# relay_driver.net
KiCad netlist of a schematic drawn in EAGLE
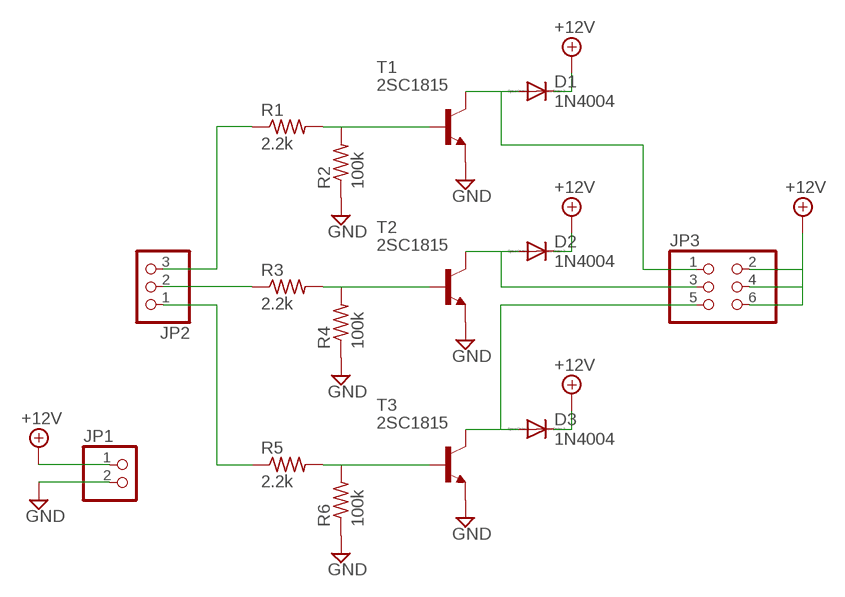
[diagram p0: schematic, sheet 1]

(export (version "E")
  (design (tool "Eeschema 10.0.6"))
  (components
    (comp (ref "D1")
      (value "1N4004")
      (footprint "eagle-import:DO41-10")
      (libsource (lib "eagle-import") (part "1N4004"))
    )
    (comp (ref "D2")
      (value "1N4004")
      (footprint "eagle-import:DO41-10")
      (libsource (lib "eagle-import") (part "1N4004"))
    )
    (comp (ref "D3")
      (value "1N4004")
      (footprint "eagle-import:DO41-10")
      (libsource (lib "eagle-import") (part "1N4004"))
    )
    (comp (ref "JP1")
      (value "PINHD-1X2")
      (footprint "eagle-import:1X02")
      (libsource (lib "eagle-import") (part "PINHD-1X2"))
    )
    (comp (ref "JP2")
      (value "PINHD-1X3")
      (footprint "eagle-import:1X03")
      (libsource (lib "eagle-import") (part "PINHD-1X3"))
    )
    (comp (ref "JP3")
      (value "PINHD-2X3")
      (footprint "eagle-import:2X03")
      (libsource (lib "eagle-import") (part "PINHD-2X3"))
    )
    (comp (ref "R1")
      (value "2.2k")
      (footprint "eagle-import:0204_7")
      (libsource (lib "eagle-import") (part "R-US_0204/7"))
    )
    (comp (ref "R2")
      (value "100k")
      (footprint "eagle-import:0204_7")
      (libsource (lib "eagle-import") (part "R-US_0204/7"))
    )
    (comp (ref "R3")
      (value "2.2k")
      (footprint "eagle-import:0204_7")
      (libsource (lib "eagle-import") (part "R-US_0204/7"))
    )
    (comp (ref "R4")
      (value "100k")
      (footprint "eagle-import:0204_7")
      (libsource (lib "eagle-import") (part "R-US_0204/7"))
    )
    (comp (ref "R5")
      (value "2.2k")
      (footprint "eagle-import:0204_7")
      (libsource (lib "eagle-import") (part "R-US_0204/7"))
    )
    (comp (ref "R6")
      (value "100k")
      (footprint "eagle-import:0204_7")
      (libsource (lib "eagle-import") (part "R-US_0204/7"))
    )
    (comp (ref "T1")
      (value "2SC1815")
      (footprint "eagle-import:TO92-ECB")
      (libsource (lib "eagle-import") (part "2SC1815"))
    )
    (comp (ref "T2")
      (value "2SC1815")
      (footprint "eagle-import:TO92-ECB")
      (libsource (lib "eagle-import") (part "2SC1815"))
    )
    (comp (ref "T3")
      (value "2SC1815")
      (footprint "eagle-import:TO92-ECB")
      (libsource (lib "eagle-import") (part "2SC1815"))
    )
  )
  (nets
    (net (code "1") (name "+12V") (class "Default")
      (node (ref "D1") (pin "C") (pinfunction "C_C") (pintype "passive"))
      (node (ref "D2") (pin "C") (pinfunction "C_C") (pintype "passive"))
      (node (ref "D3") (pin "C") (pinfunction "C_C") (pintype "passive"))
      (node (ref "JP1") (pin "1") (pinfunction "1_1") (pintype "passive"))
      (node (ref "JP3") (pin "2") (pinfunction "2_2") (pintype "passive"))
      (node (ref "JP3") (pin "4") (pinfunction "4_4") (pintype "passive"))
      (node (ref "JP3") (pin "6") (pinfunction "6_6") (pintype "passive"))
    )
    (net (code "2") (name "GND") (class "Default")
      (node (ref "JP1") (pin "2") (pinfunction "2_2") (pintype "passive"))
      (node (ref "R2") (pin "1") (pinfunction "1_1") (pintype "passive"))
      (node (ref "R4") (pin "1") (pinfunction "1_1") (pintype "passive"))
      (node (ref "R6") (pin "1") (pinfunction "1_1") (pintype "passive"))
      (node (ref "T1") (pin "E") (pinfunction "E_E") (pintype "passive"))
      (node (ref "T2") (pin "E") (pinfunction "E_E") (pintype "passive"))
      (node (ref "T3") (pin "E") (pinfunction "E_E") (pintype "passive"))
    )
    (net (code "3") (name "Net-(D1-PadA)") (class "Default")
      (node (ref "D1") (pin "A") (pinfunction "A_A") (pintype "passive"))
      (node (ref "JP3") (pin "1") (pinfunction "1_1") (pintype "passive"))
      (node (ref "T1") (pin "C") (pinfunction "C_C") (pintype "passive"))
    )
    (net (code "4") (name "Net-(D2-PadA)") (class "Default")
      (node (ref "D2") (pin "A") (pinfunction "A_A") (pintype "passive"))
      (node (ref "JP3") (pin "3") (pinfunction "3_3") (pintype "passive"))
      (node (ref "T2") (pin "C") (pinfunction "C_C") (pintype "passive"))
    )
    (net (code "5") (name "Net-(D3-PadA)") (class "Default")
      (node (ref "D3") (pin "A") (pinfunction "A_A") (pintype "passive"))
      (node (ref "JP3") (pin "5") (pinfunction "5_5") (pintype "passive"))
      (node (ref "T3") (pin "C") (pinfunction "C_C") (pintype "passive"))
    )
    (net (code "6") (name "Net-(JP2-Pad1)") (class "Default")
      (node (ref "JP2") (pin "1") (pinfunction "1_1") (pintype "passive"))
      (node (ref "R5") (pin "1") (pinfunction "1_1") (pintype "passive"))
    )
    (net (code "7") (name "Net-(JP2-Pad2)") (class "Default")
      (node (ref "JP2") (pin "2") (pinfunction "2_2") (pintype "passive"))
      (node (ref "R3") (pin "1") (pinfunction "1_1") (pintype "passive"))
    )
    (net (code "8") (name "Net-(JP2-Pad3)") (class "Default")
      (node (ref "JP2") (pin "3") (pinfunction "3_3") (pintype "passive"))
      (node (ref "R1") (pin "1") (pinfunction "1_1") (pintype "passive"))
    )
    (net (code "9") (name "Net-(R1-Pad2)") (class "Default")
      (node (ref "R1") (pin "2") (pinfunction "2_2") (pintype "passive"))
      (node (ref "R2") (pin "2") (pinfunction "2_2") (pintype "passive"))
      (node (ref "T1") (pin "B") (pinfunction "B_B") (pintype "passive"))
    )
    (net (code "10") (name "Net-(R3-Pad2)") (class "Default")
      (node (ref "R3") (pin "2") (pinfunction "2_2") (pintype "passive"))
      (node (ref "R4") (pin "2") (pinfunction "2_2") (pintype "passive"))
      (node (ref "T2") (pin "B") (pinfunction "B_B") (pintype "passive"))
    )
    (net (code "11") (name "Net-(R5-Pad2)") (class "Default")
      (node (ref "R5") (pin "2") (pinfunction "2_2") (pintype "passive"))
      (node (ref "R6") (pin "2") (pinfunction "2_2") (pintype "passive"))
      (node (ref "T3") (pin "B") (pinfunction "B_B") (pintype "passive"))
    )
  )
)
